# transfer-block.net
KiCad netlist of a schematic drawn in EAGLE
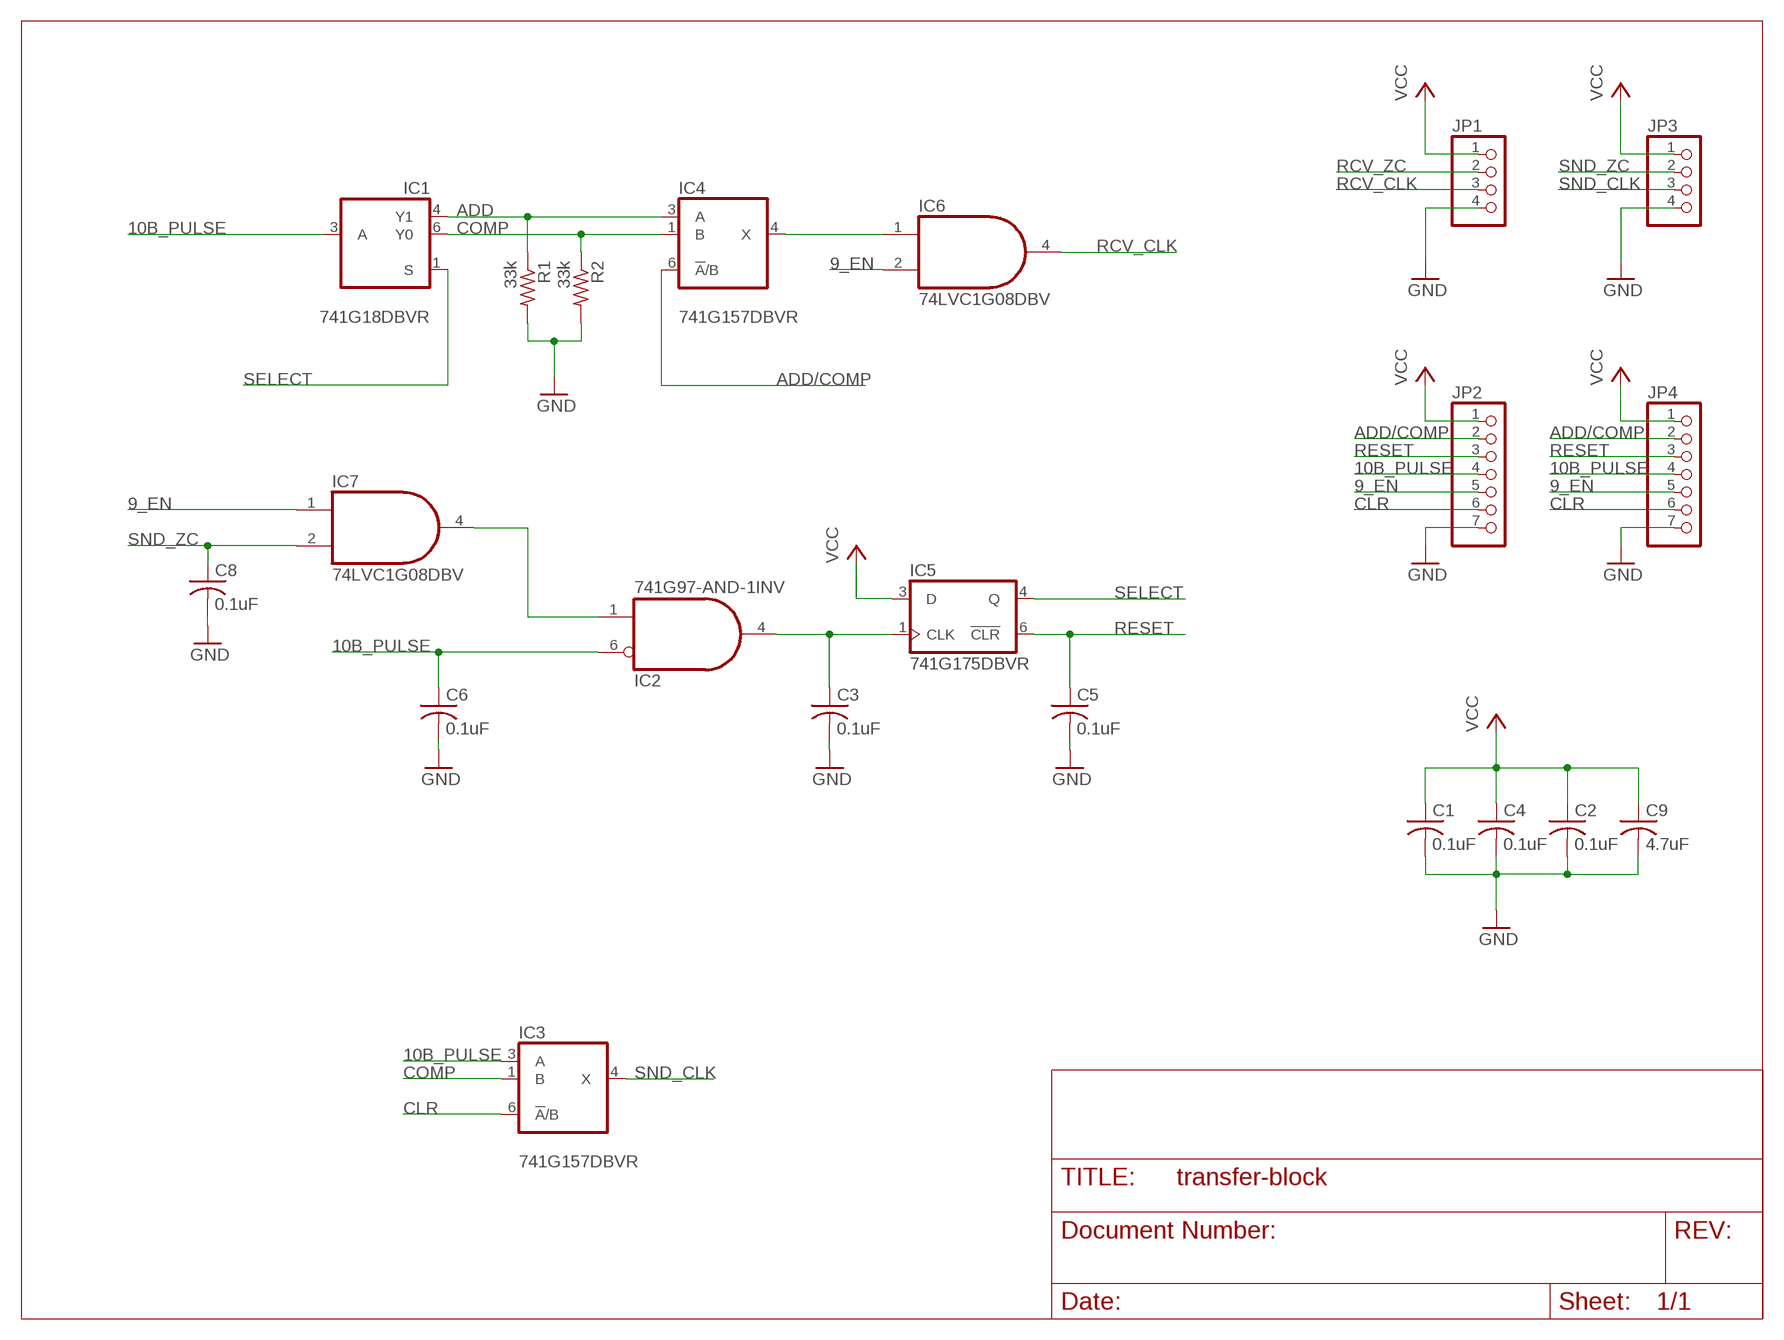
[diagram p0: schematic, sheet 1]

(export (version "E")
  (design (tool "Eeschema 10.0.6"))
  (components
    (comp (ref "C1")
      (value "0.1uF")
      (footprint "eagle-import:C0603K")
      (libsource (lib "eagle-import") (part "C-USC0603K"))
    )
    (comp (ref "C2")
      (value "0.1uF")
      (footprint "eagle-import:C0603K")
      (libsource (lib "eagle-import") (part "C-USC0603K"))
    )
    (comp (ref "C3")
      (value "0.1uF")
      (footprint "eagle-import:C0603K")
      (libsource (lib "eagle-import") (part "C-USC0603K"))
    )
    (comp (ref "C4")
      (value "0.1uF")
      (footprint "eagle-import:C0603K")
      (libsource (lib "eagle-import") (part "C-USC0603K"))
    )
    (comp (ref "C5")
      (value "0.1uF")
      (footprint "eagle-import:C0603K")
      (libsource (lib "eagle-import") (part "C-USC0603K"))
    )
    (comp (ref "C6")
      (value "0.1uF")
      (footprint "eagle-import:C0603K")
      (libsource (lib "eagle-import") (part "C-USC0603K"))
    )
    (comp (ref "C8")
      (value "0.1uF")
      (footprint "eagle-import:C0603K")
      (libsource (lib "eagle-import") (part "C-USC0603K"))
    )
    (comp (ref "C9")
      (value "4.7uF")
      (footprint "eagle-import:C0603K")
      (libsource (lib "eagle-import") (part "C-USC0603K"))
    )
    (comp (ref "IC1")
      (value "741G18DBVR")
      (footprint "eagle-import:DBV_R-PDSO-G6")
      (libsource (lib "eagle-import") (part "741G18"))
    )
    (comp (ref "IC2")
      (value "741G97-AND-1INV")
      (footprint "eagle-import:DBV_R-PDSO-G6")
      (libsource (lib "eagle-import") (part "741G97-AND-1INV"))
    )
    (comp (ref "IC3")
      (value "741G157DBVR")
      (footprint "eagle-import:DBV_R-PDSO-G6")
      (libsource (lib "eagle-import") (part "741G3157DBVR"))
    )
    (comp (ref "IC4")
      (value "741G157DBVR")
      (footprint "eagle-import:DBV_R-PDSO-G6")
      (libsource (lib "eagle-import") (part "741G3157DBVR"))
    )
    (comp (ref "IC5")
      (value "741G175DBVR")
      (footprint "eagle-import:DBV_R-PDSO-G6")
      (libsource (lib "eagle-import") (part "741G175"))
    )
    (comp (ref "IC6")
      (value "74LVC1G08DBV")
      (footprint "eagle-import:SOT23-5")
      (libsource (lib "eagle-import") (part "741G08DBVLVC"))
    )
    (comp (ref "IC7")
      (value "74LVC1G08DBV")
      (footprint "eagle-import:SOT23-5")
      (libsource (lib "eagle-import") (part "741G08DBVLVC"))
    )
    (comp (ref "JP1")
      (value "PINHD-1X4")
      (footprint "eagle-import:1X04")
      (libsource (lib "eagle-import") (part "PINHD-1X4"))
    )
    (comp (ref "JP2")
      (value "PINHD-1X7")
      (footprint "eagle-import:1X07")
      (libsource (lib "eagle-import") (part "PINHD-1X7"))
    )
    (comp (ref "JP3")
      (value "PINHD-1X4")
      (footprint "eagle-import:1X04")
      (libsource (lib "eagle-import") (part "PINHD-1X4"))
    )
    (comp (ref "JP4")
      (value "PINHD-1X7")
      (footprint "eagle-import:1X07")
      (libsource (lib "eagle-import") (part "PINHD-1X7"))
    )
    (comp (ref "R1")
      (value "33k")
      (footprint "eagle-import:R0603")
      (libsource (lib "eagle-import") (part "R-US_R0603"))
    )
    (comp (ref "R2")
      (value "33k")
      (footprint "eagle-import:R0603")
      (libsource (lib "eagle-import") (part "R-US_R0603"))
    )
  )
  (nets
    (net (code "1") (name "/9_EN") (class "Default")
      (node (ref "IC6") (pin "2") (pinfunction "I1_2") (pintype "input"))
      (node (ref "IC7") (pin "1") (pinfunction "I0_1") (pintype "input"))
      (node (ref "JP2") (pin "5") (pinfunction "5_5") (pintype "passive"))
      (node (ref "JP4") (pin "5") (pinfunction "5_5") (pintype "passive"))
    )
    (net (code "2") (name "/10B_PULSE") (class "Default")
      (node (ref "C6") (pin "1") (pinfunction "1_1") (pintype "passive"))
      (node (ref "IC1") (pin "3") (pinfunction "A_3") (pintype "bidirectional"))
      (node (ref "IC2") (pin "6") (pinfunction "I0_6") (pintype "input"))
      (node (ref "IC3") (pin "3") (pinfunction "A_3") (pintype "bidirectional"))
      (node (ref "JP2") (pin "4") (pinfunction "4_4") (pintype "passive"))
      (node (ref "JP4") (pin "4") (pinfunction "4_4") (pintype "passive"))
    )
    (net (code "3") (name "/ADD") (class "Default")
      (node (ref "IC1") (pin "4") (pinfunction "Y1_4") (pintype "bidirectional"))
      (node (ref "IC4") (pin "3") (pinfunction "A_3") (pintype "bidirectional"))
      (node (ref "R1") (pin "1") (pinfunction "1_1") (pintype "passive"))
    )
    (net (code "4") (name "/ADD{slash}COMP") (class "Default")
      (node (ref "IC4") (pin "6") (pinfunction "~{A}/B_6") (pintype "input"))
      (node (ref "JP2") (pin "2") (pinfunction "2_2") (pintype "passive"))
      (node (ref "JP4") (pin "2") (pinfunction "2_2") (pintype "passive"))
    )
    (net (code "5") (name "/CLR") (class "Default")
      (node (ref "IC3") (pin "6") (pinfunction "~{A}/B_6") (pintype "input"))
      (node (ref "JP2") (pin "6") (pinfunction "6_6") (pintype "passive"))
      (node (ref "JP4") (pin "6") (pinfunction "6_6") (pintype "passive"))
    )
    (net (code "6") (name "/COMP") (class "Default")
      (node (ref "IC1") (pin "6") (pinfunction "Y0_6") (pintype "bidirectional"))
      (node (ref "IC3") (pin "1") (pinfunction "B_1") (pintype "bidirectional"))
      (node (ref "IC4") (pin "1") (pinfunction "B_1") (pintype "bidirectional"))
      (node (ref "R2") (pin "1") (pinfunction "1_1") (pintype "passive"))
    )
    (net (code "7") (name "/RCV_CLK") (class "Default")
      (node (ref "IC6") (pin "4") (pinfunction "O_4") (pintype "output"))
      (node (ref "JP1") (pin "3") (pinfunction "3_3") (pintype "passive"))
    )
    (net (code "8") (name "/RCV_ZC") (class "Default")
      (node (ref "JP1") (pin "2") (pinfunction "2_2") (pintype "passive"))
    )
    (net (code "9") (name "/RESET") (class "Default")
      (node (ref "C5") (pin "1") (pinfunction "1_1") (pintype "passive"))
      (node (ref "IC5") (pin "6") (pinfunction "~{CLR}_6") (pintype "input"))
      (node (ref "JP2") (pin "3") (pinfunction "3_3") (pintype "passive"))
      (node (ref "JP4") (pin "3") (pinfunction "3_3") (pintype "passive"))
    )
    (net (code "10") (name "/SELECT") (class "Default")
      (node (ref "IC1") (pin "1") (pinfunction "S_1") (pintype "input"))
      (node (ref "IC5") (pin "4") (pinfunction "Q_4") (pintype "output"))
    )
    (net (code "11") (name "/SND_CLK") (class "Default")
      (node (ref "IC3") (pin "4") (pinfunction "X_4") (pintype "bidirectional"))
      (node (ref "JP3") (pin "3") (pinfunction "3_3") (pintype "passive"))
    )
    (net (code "12") (name "/SND_ZC") (class "Default")
      (node (ref "C8") (pin "1") (pinfunction "1_1") (pintype "passive"))
      (node (ref "IC7") (pin "2") (pinfunction "I1_2") (pintype "input"))
      (node (ref "JP3") (pin "2") (pinfunction "2_2") (pintype "passive"))
    )
    (net (code "13") (name "GND") (class "Default")
      (node (ref "C1") (pin "2") (pinfunction "2_2") (pintype "passive"))
      (node (ref "C2") (pin "2") (pinfunction "2_2") (pintype "passive"))
      (node (ref "C3") (pin "2") (pinfunction "2_2") (pintype "passive"))
      (node (ref "C4") (pin "2") (pinfunction "2_2") (pintype "passive"))
      (node (ref "C5") (pin "2") (pinfunction "2_2") (pintype "passive"))
      (node (ref "C6") (pin "2") (pinfunction "2_2") (pintype "passive"))
      (node (ref "C8") (pin "2") (pinfunction "2_2") (pintype "passive"))
      (node (ref "C9") (pin "2") (pinfunction "2_2") (pintype "passive"))
      (node (ref "JP1") (pin "4") (pinfunction "4_4") (pintype "passive"))
      (node (ref "JP2") (pin "7") (pinfunction "7_7") (pintype "passive"))
      (node (ref "JP3") (pin "4") (pinfunction "4_4") (pintype "passive"))
      (node (ref "JP4") (pin "7") (pinfunction "7_7") (pintype "passive"))
      (node (ref "R1") (pin "2") (pinfunction "2_2") (pintype "passive"))
      (node (ref "R2") (pin "2") (pinfunction "2_2") (pintype "passive"))
    )
    (net (code "14") (name "Net-(IC2A-I1)") (class "Default")
      (node (ref "IC2") (pin "1") (pinfunction "I1_1") (pintype "input"))
      (node (ref "IC7") (pin "4") (pinfunction "O_4") (pintype "output"))
    )
    (net (code "15") (name "Net-(IC2A-O)") (class "Default")
      (node (ref "C3") (pin "1") (pinfunction "1_1") (pintype "passive"))
      (node (ref "IC2") (pin "4") (pinfunction "O_4") (pintype "output"))
      (node (ref "IC5") (pin "1") (pinfunction "CLK_1") (pintype "input"))
    )
    (net (code "16") (name "Net-(IC4A-X)") (class "Default")
      (node (ref "IC4") (pin "4") (pinfunction "X_4") (pintype "bidirectional"))
      (node (ref "IC6") (pin "1") (pinfunction "I0_1") (pintype "input"))
    )
    (net (code "17") (name "VCC") (class "Default")
      (node (ref "C1") (pin "1") (pinfunction "1_1") (pintype "passive"))
      (node (ref "C2") (pin "1") (pinfunction "1_1") (pintype "passive"))
      (node (ref "C4") (pin "1") (pinfunction "1_1") (pintype "passive"))
      (node (ref "C9") (pin "1") (pinfunction "1_1") (pintype "passive"))
      (node (ref "IC5") (pin "3") (pinfunction "D_3") (pintype "input"))
      (node (ref "JP1") (pin "1") (pinfunction "1_1") (pintype "passive"))
      (node (ref "JP2") (pin "1") (pinfunction "1_1") (pintype "passive"))
      (node (ref "JP3") (pin "1") (pinfunction "1_1") (pintype "passive"))
      (node (ref "JP4") (pin "1") (pinfunction "1_1") (pintype "passive"))
    )
  )
)
